# amplifier_sp.net
KiCad netlist of a schematic drawn in Altium Designer
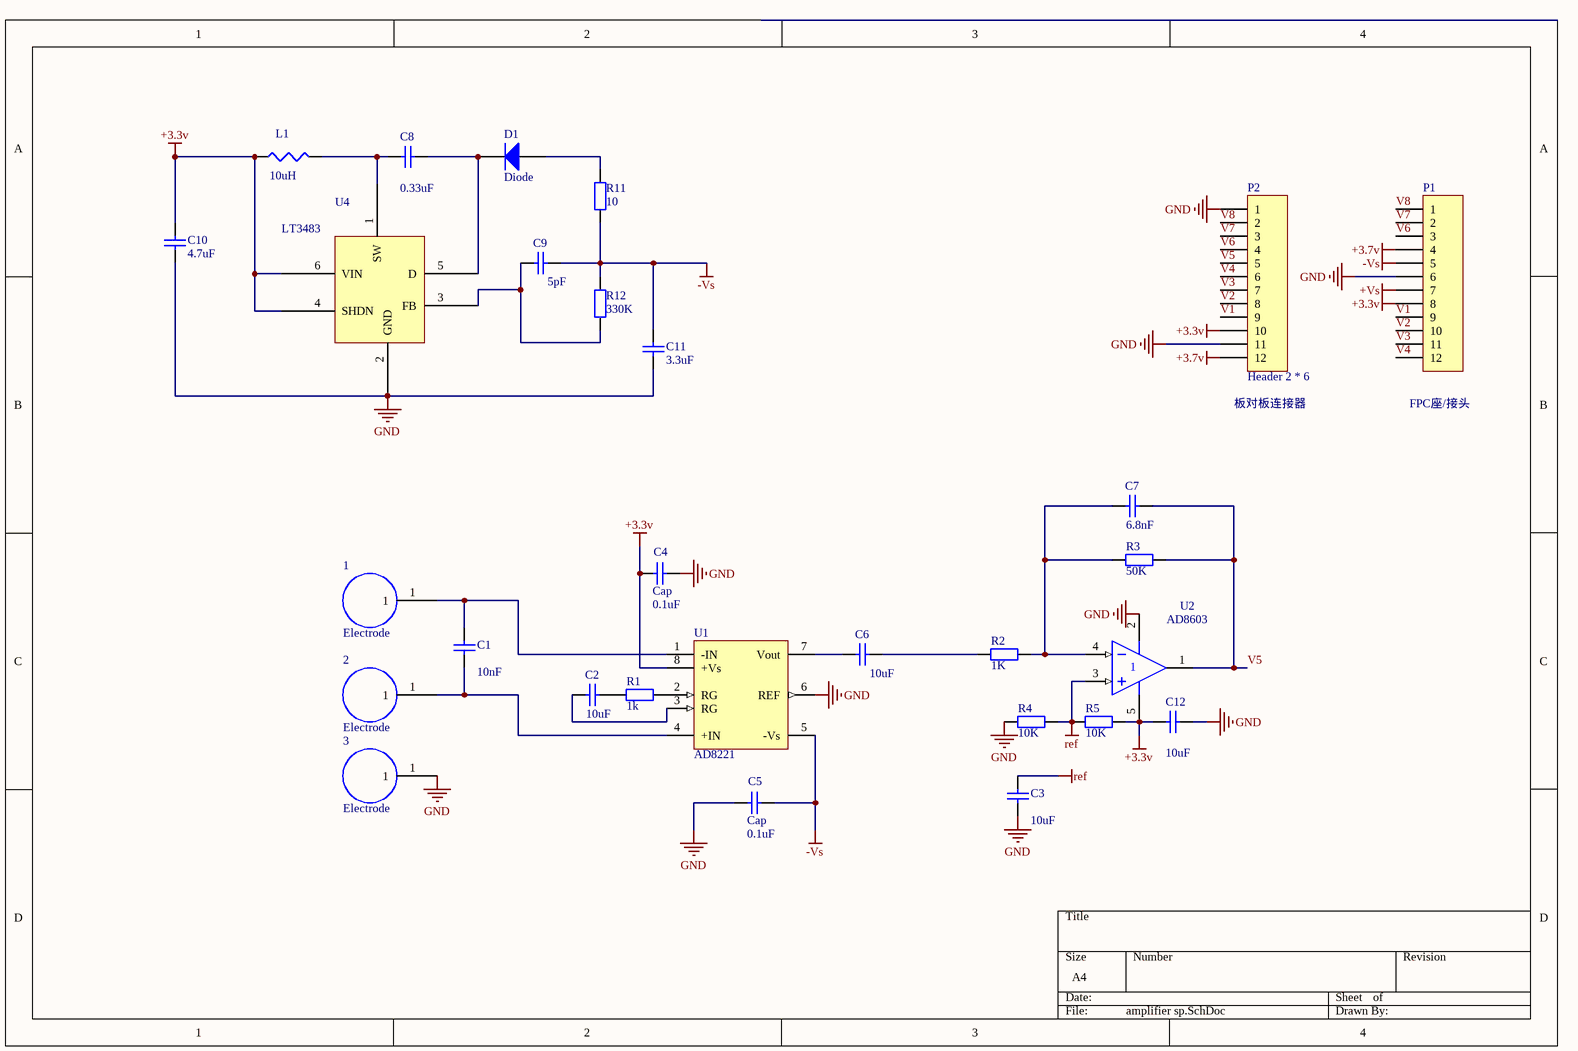
[diagram p0: amplifier sp.SchDoc]

(export (version "E")
  (design (tool "Eeschema 10.0.6"))
  (components
    (comp (ref "1")
      (value "Electrode")
      (footprint "elec-diff")
      (libsource (lib "My Sch Library") (part "Electrode"))
    )
    (comp (ref "2")
      (value "Electrode")
      (footprint "elec-diff")
      (libsource (lib "My Sch Library") (part "Electrode"))
    )
    (comp (ref "3")
      (value "Electrode")
      (footprint "elec-ref")
      (libsource (lib "My Sch Library") (part "Electrode"))
    )
    (comp (ref "C1")
      (value "10nF")
      (footprint "1608[0603]")
      (description "Capacitor")
      (fields (field (name "PUBLISHER") "Altium Limited"))
      (libsource (lib "Miscellaneous Devices") (part "Cap"))
    )
    (comp (ref "C2")
      (value "10uF")
      (footprint "1608[0603]")
      (description "Capacitor")
      (fields (field (name "PUBLISHER") "Altium Limited"))
      (libsource (lib "Miscellaneous Devices") (part "Cap"))
    )
    (comp (ref "C3")
      (value "10uF")
      (footprint "1608[0603]")
      (description "Capacitor")
      (fields (field (name "PUBLISHER") "Altium Limited"))
      (libsource (lib "Miscellaneous Devices") (part "Cap"))
    )
    (comp (ref "C4")
      (value "Cap")
      (footprint "1608[0603]")
      (description "Capacitor")
      (fields (field (name "ALTIUM_VALUE") "0.1uF") (field (name "PUBLISHER") "Altium Limited"))
      (libsource (lib "Miscellaneous Devices") (part "Cap"))
    )
    (comp (ref "C5")
      (value "Cap")
      (footprint "1608[0603]")
      (description "Capacitor")
      (fields (field (name "ALTIUM_VALUE") "0.1uF") (field (name "PUBLISHER") "Altium Limited"))
      (libsource (lib "Miscellaneous Devices") (part "Cap"))
    )
    (comp (ref "C6")
      (value "10uF")
      (footprint "1608[0603]")
      (description "Capacitor")
      (fields (field (name "PUBLISHER") "Altium Limited"))
      (libsource (lib "Miscellaneous Devices") (part "Cap"))
    )
    (comp (ref "C7")
      (value "6.8nF")
      (footprint "1608[0603]")
      (description "Capacitor")
      (fields (field (name "PUBLISHER") "Altium Limited"))
      (libsource (lib "Miscellaneous Devices") (part "Cap"))
    )
    (comp (ref "C8")
      (value "0.33uF")
      (footprint "1608[0603]")
      (description "Capacitor (Semiconductor SIM Model)")
      (fields (field (name "Comment") "Cap Semi") (field (name "PUBLISHER") "Altium Limited"))
      (libsource (lib "Miscellaneous Devices") (part "Cap Semi"))
    )
    (comp (ref "C9")
      (value "5pF")
      (footprint "1608[0603]")
      (description "Capacitor (Semiconductor SIM Model)")
      (fields (field (name "Comment") "Cap Semi") (field (name "PUBLISHER") "Altium Limited"))
      (libsource (lib "Miscellaneous Devices") (part "Cap Semi"))
    )
    (comp (ref "C10")
      (value "4.7uF")
      (footprint "1608[0603]")
      (description "Capacitor (Semiconductor SIM Model)")
      (fields (field (name "Comment") "Cap Semi") (field (name "PUBLISHER") "Altium Limited"))
      (libsource (lib "Miscellaneous Devices") (part "Cap Semi"))
    )
    (comp (ref "C11")
      (value "3.3uF")
      (footprint "1608[0603]")
      (description "Capacitor (Semiconductor SIM Model)")
      (fields (field (name "Comment") "Cap Semi") (field (name "PUBLISHER") "Altium Limited"))
      (libsource (lib "Miscellaneous Devices") (part "Cap Semi"))
    )
    (comp (ref "C12")
      (value "10uF")
      (footprint "1608[0603]")
      (description "Capacitor")
      (fields (field (name "PUBLISHER") "Altium Limited"))
      (libsource (lib "Miscellaneous Devices") (part "Cap"))
    )
    (comp (ref "D1")
      (value "Diode")
      (footprint "D0402")
      (description "Default Diode")
      (fields (field (name "PUBLISHER") "Altium Limited"))
      (libsource (lib "Miscellaneous Devices") (part "Diode"))
    )
    (comp (ref "L1")
      (value "10uH")
      (footprint "1608[0603]")
      (description "Resistor")
      (fields (field (name "Comment") "Res3") (field (name "PUBLISHER") "Altium Limited"))
      (libsource (lib "Miscellaneous Devices") (part "Res3"))
    )
    (comp (ref "P1")
      (value "~")
      (footprint "12P_0.5mm()FPC")
      (description "Header, 12-Pin")
      (fields (field (name "PUBLISHER") "Altium Limited"))
      (libsource (lib "Miscellaneous Connectors") (part "Header 12"))
    )
    (comp (ref "P2")
      (value "Header 2 * 6")
      (footprint "btb0.5*12top")
      (description "Header, 12-Pin")
      (fields (field (name "PUBLISHER") "Altium Limited"))
      (libsource (lib "Miscellaneous Connectors") (part "Header 12"))
    )
    (comp (ref "R1")
      (value "1k")
      (footprint "1608[0603]")
      (description "Resistor")
      (fields (field (name "PUBLISHER") "Altium Limited"))
      (libsource (lib "") (part "Res2_2"))
    )
    (comp (ref "R2")
      (value "1K")
      (footprint "1608[0603]")
      (description "Resistor")
      (fields (field (name "PUBLISHER") "Altium Limited"))
      (libsource (lib "Miscellaneous Devices") (part "Res2"))
    )
    (comp (ref "R3")
      (value "50K")
      (footprint "1608[0603]")
      (description "Resistor")
      (fields (field (name "PUBLISHER") "Altium Limited"))
      (libsource (lib "Miscellaneous Devices") (part "Res2"))
    )
    (comp (ref "R4")
      (value "10K")
      (footprint "1608[0603]")
      (description "Resistor")
      (fields (field (name "PUBLISHER") "Altium Limited"))
      (libsource (lib "Miscellaneous Devices") (part "Res2"))
    )
    (comp (ref "R5")
      (value "10K")
      (footprint "1608[0603]")
      (description "Resistor")
      (fields (field (name "PUBLISHER") "Altium Limited"))
      (libsource (lib "Miscellaneous Devices") (part "Res2"))
    )
    (comp (ref "R11")
      (value "10")
      (footprint "1608[0603]")
      (description "Resistor")
      (fields (field (name "PUBLISHER") "Altium Limited"))
      (libsource (lib "") (part "Res2_1"))
    )
    (comp (ref "R12")
      (value "330K")
      (footprint "1608[0603]")
      (description "Resistor")
      (fields (field (name "PUBLISHER") "Altium Limited"))
      (libsource (lib "") (part "Res2_1"))
    )
    (comp (ref "U1")
      (value "AD8221")
      (footprint "MSOP-8")
      (description "Precision, Low-Power Instrumentation Amplifiers")
      (fields (field (name "PUBLISHER") "Altium Limited"))
      (libsource (lib "BB Instrumentation Amplifier") (part "INA128UA"))
    )
    (comp (ref "U2")
      (value "AD8603")
      (footprint "SOT23-5AM")
      (libsource (lib "My Sch Library") (part "AD8603"))
    )
    (comp (ref "U4") (value "LT3483") (footprint "LT3843") (libsource (lib "controler") (part "LT3483")))
  )
  (nets
    (net (code "1") (name "+3.3v") (class "Default")
      (node (ref "C10") (pin "2") (pinfunction "2_2") (pintype "passive"))
      (node (ref "C12") (pin "2") (pinfunction "2_2") (pintype "passive"))
      (node (ref "C4") (pin "1") (pinfunction "1_1") (pintype "passive"))
      (node (ref "L1") (pin "1") (pinfunction "1_1") (pintype "passive"))
      (node (ref "P1") (pin "8") (pinfunction "8_8") (pintype "passive"))
      (node (ref "P2") (pin "10") (pinfunction "10_10") (pintype "passive"))
      (node (ref "R5") (pin "2") (pinfunction "2_2") (pintype "passive"))
      (node (ref "U1") (pin "8") (pinfunction "+Vs_8") (pintype "passive"))
      (node (ref "U2") (pin "5") (pinfunction "V-_5") (pintype "power_in"))
      (node (ref "U4") (pin "4") (pinfunction "SHDN_4") (pintype "passive"))
      (node (ref "U4") (pin "6") (pinfunction "VIN_6") (pintype "passive"))
    )
    (net (code "2") (name "+3.7v") (class "Default")
      (node (ref "P1") (pin "4") (pinfunction "4_4") (pintype "passive"))
      (node (ref "P2") (pin "12") (pinfunction "12_12") (pintype "passive"))
    )
    (net (code "3") (name "+Vs") (class "Default")
      (node (ref "P1") (pin "7") (pinfunction "7_7") (pintype "passive"))
    )
    (net (code "4") (name "-Vs") (class "Default")
      (node (ref "C11") (pin "1") (pinfunction "1_1") (pintype "passive"))
      (node (ref "C5") (pin "2") (pinfunction "2_2") (pintype "passive"))
      (node (ref "C9") (pin "2") (pinfunction "2_2") (pintype "passive"))
      (node (ref "P1") (pin "5") (pinfunction "5_5") (pintype "passive"))
      (node (ref "R11") (pin "2") (pinfunction "2_2") (pintype "passive"))
      (node (ref "R12") (pin "1") (pinfunction "1_1") (pintype "passive"))
      (node (ref "U1") (pin "5") (pinfunction "-Vs_5") (pintype "passive"))
    )
    (net (code "5") (name "/V1") (class "Default")
      (node (ref "P1") (pin "9") (pinfunction "9_9") (pintype "passive"))
      (node (ref "P2") (pin "9") (pinfunction "9_9") (pintype "passive"))
    )
    (net (code "6") (name "/V2") (class "Default")
      (node (ref "P1") (pin "10") (pinfunction "10_10") (pintype "passive"))
      (node (ref "P2") (pin "8") (pinfunction "8_8") (pintype "passive"))
    )
    (net (code "7") (name "/V3") (class "Default")
      (node (ref "P1") (pin "11") (pinfunction "11_11") (pintype "passive"))
      (node (ref "P2") (pin "7") (pinfunction "7_7") (pintype "passive"))
    )
    (net (code "8") (name "/V4") (class "Default")
      (node (ref "P1") (pin "12") (pinfunction "12_12") (pintype "passive"))
      (node (ref "P2") (pin "6") (pinfunction "6_6") (pintype "passive"))
    )
    (net (code "9") (name "/V5") (class "Default")
      (node (ref "C7") (pin "1") (pinfunction "1_1") (pintype "passive"))
      (node (ref "P2") (pin "5") (pinfunction "5_5") (pintype "passive"))
      (node (ref "R3") (pin "2") (pinfunction "2_2") (pintype "passive"))
      (node (ref "U2") (pin "1") (pinfunction "OUT_1") (pintype "passive"))
    )
    (net (code "10") (name "/V6") (class "Default")
      (node (ref "P1") (pin "3") (pinfunction "3_3") (pintype "passive"))
      (node (ref "P2") (pin "4") (pinfunction "4_4") (pintype "passive"))
    )
    (net (code "11") (name "/V7") (class "Default")
      (node (ref "P1") (pin "2") (pinfunction "2_2") (pintype "passive"))
      (node (ref "P2") (pin "3") (pinfunction "3_3") (pintype "passive"))
    )
    (net (code "12") (name "/V8") (class "Default")
      (node (ref "P1") (pin "1") (pinfunction "1_1") (pintype "passive"))
      (node (ref "P2") (pin "2") (pinfunction "2_2") (pintype "passive"))
    )
    (net (code "13") (name "GND") (class "Default")
      (node (ref "3") (pin "1") (pinfunction "1_1") (pintype "passive"))
      (node (ref "C10") (pin "1") (pinfunction "1_1") (pintype "passive"))
      (node (ref "C11") (pin "2") (pinfunction "2_2") (pintype "passive"))
      (node (ref "C12") (pin "1") (pinfunction "1_1") (pintype "passive"))
      (node (ref "C3") (pin "1") (pinfunction "1_1") (pintype "passive"))
      (node (ref "C4") (pin "2") (pinfunction "2_2") (pintype "passive"))
      (node (ref "C5") (pin "1") (pinfunction "1_1") (pintype "passive"))
      (node (ref "P1") (pin "6") (pinfunction "6_6") (pintype "passive"))
      (node (ref "P2") (pin "1") (pinfunction "1_1") (pintype "passive"))
      (node (ref "P2") (pin "11") (pinfunction "11_11") (pintype "passive"))
      (node (ref "R4") (pin "1") (pinfunction "1_1") (pintype "passive"))
      (node (ref "U1") (pin "6") (pinfunction "REF_6") (pintype "output"))
      (node (ref "U2") (pin "2") (pinfunction "V+_2") (pintype "power_in"))
      (node (ref "U4") (pin "2") (pinfunction "GND_2") (pintype "passive"))
    )
    (net (code "14") (name "Net-(C2-Pad1)") (class "Default")
      (node (ref "C2") (pin "1") (pinfunction "1_1") (pintype "passive"))
      (node (ref "R1") (pin "2") (pinfunction "2_2") (pintype "passive"))
    )
    (net (code "15") (name "Net-(C2-Pad2)") (class "Default")
      (node (ref "C2") (pin "2") (pinfunction "2_2") (pintype "passive"))
      (node (ref "U1") (pin "3") (pinfunction "RG_3") (pintype "input"))
    )
    (net (code "16") (name "Net-(C6-Pad1)") (class "Default")
      (node (ref "C6") (pin "1") (pinfunction "1_1") (pintype "passive"))
      (node (ref "R2") (pin "1") (pinfunction "1_1") (pintype "passive"))
    )
    (net (code "17") (name "Net-(D1-A)") (class "Default")
      (node (ref "D1") (pin "1") (pinfunction "A_1") (pintype "passive"))
      (node (ref "R11") (pin "1") (pinfunction "1_1") (pintype "passive"))
    )
    (net (code "18") (name "Net-(D1-K)") (class "Default")
      (node (ref "C8") (pin "2") (pinfunction "2_2") (pintype "passive"))
      (node (ref "D1") (pin "2") (pinfunction "K_2") (pintype "passive"))
      (node (ref "U4") (pin "5") (pinfunction "D_5") (pintype "passive"))
    )
    (net (code "19") (name "Net-(R1-Pad1)") (class "Default")
      (node (ref "R1") (pin "1") (pinfunction "1_1") (pintype "passive"))
      (node (ref "U1") (pin "2") (pinfunction "RG_2") (pintype "input"))
    )
    (net (code "20") (name "Net-(U1-+IN)") (class "Default")
      (node (ref "2") (pin "1") (pinfunction "1_1") (pintype "passive"))
      (node (ref "C1") (pin "1") (pinfunction "1_1") (pintype "passive"))
      (node (ref "U1") (pin "4") (pinfunction "+IN_4") (pintype "power_in"))
    )
    (net (code "21") (name "Net-(U1--IN)") (class "Default")
      (node (ref "1") (pin "1") (pinfunction "1_1") (pintype "passive"))
      (node (ref "C1") (pin "2") (pinfunction "2_2") (pintype "passive"))
      (node (ref "U1") (pin "1") (pinfunction "-IN_1") (pintype "passive"))
    )
    (net (code "22") (name "Net-(U1-Vout)") (class "Default")
      (node (ref "C6") (pin "2") (pinfunction "2_2") (pintype "passive"))
      (node (ref "U1") (pin "7") (pinfunction "Vout_7") (pintype "power_in"))
    )
    (net (code "23") (name "Net-(U2-IN-)") (class "Default")
      (node (ref "C7") (pin "2") (pinfunction "2_2") (pintype "passive"))
      (node (ref "R2") (pin "2") (pinfunction "2_2") (pintype "passive"))
      (node (ref "R3") (pin "1") (pinfunction "1_1") (pintype "passive"))
      (node (ref "U2") (pin "4") (pinfunction "IN-_4") (pintype "input"))
    )
    (net (code "24") (name "Net-(U4-FB)") (class "Default")
      (node (ref "C9") (pin "1") (pinfunction "1_1") (pintype "passive"))
      (node (ref "R12") (pin "2") (pinfunction "2_2") (pintype "passive"))
      (node (ref "U4") (pin "3") (pinfunction "FB_3") (pintype "passive"))
    )
    (net (code "25") (name "Net-(U4-SW)") (class "Default")
      (node (ref "C8") (pin "1") (pinfunction "1_1") (pintype "passive"))
      (node (ref "L1") (pin "2") (pinfunction "2_2") (pintype "passive"))
      (node (ref "U4") (pin "1") (pinfunction "SW_1") (pintype "passive"))
    )
    (net (code "26") (name "ref") (class "Default")
      (node (ref "C3") (pin "2") (pinfunction "2_2") (pintype "passive"))
      (node (ref "R4") (pin "2") (pinfunction "2_2") (pintype "passive"))
      (node (ref "R5") (pin "1") (pinfunction "1_1") (pintype "passive"))
      (node (ref "U2") (pin "3") (pinfunction "IN+_3") (pintype "input"))
    )
  )
)
